# 09_RF_Loopback.net
KiCad netlist of a schematic drawn in Altium Designer
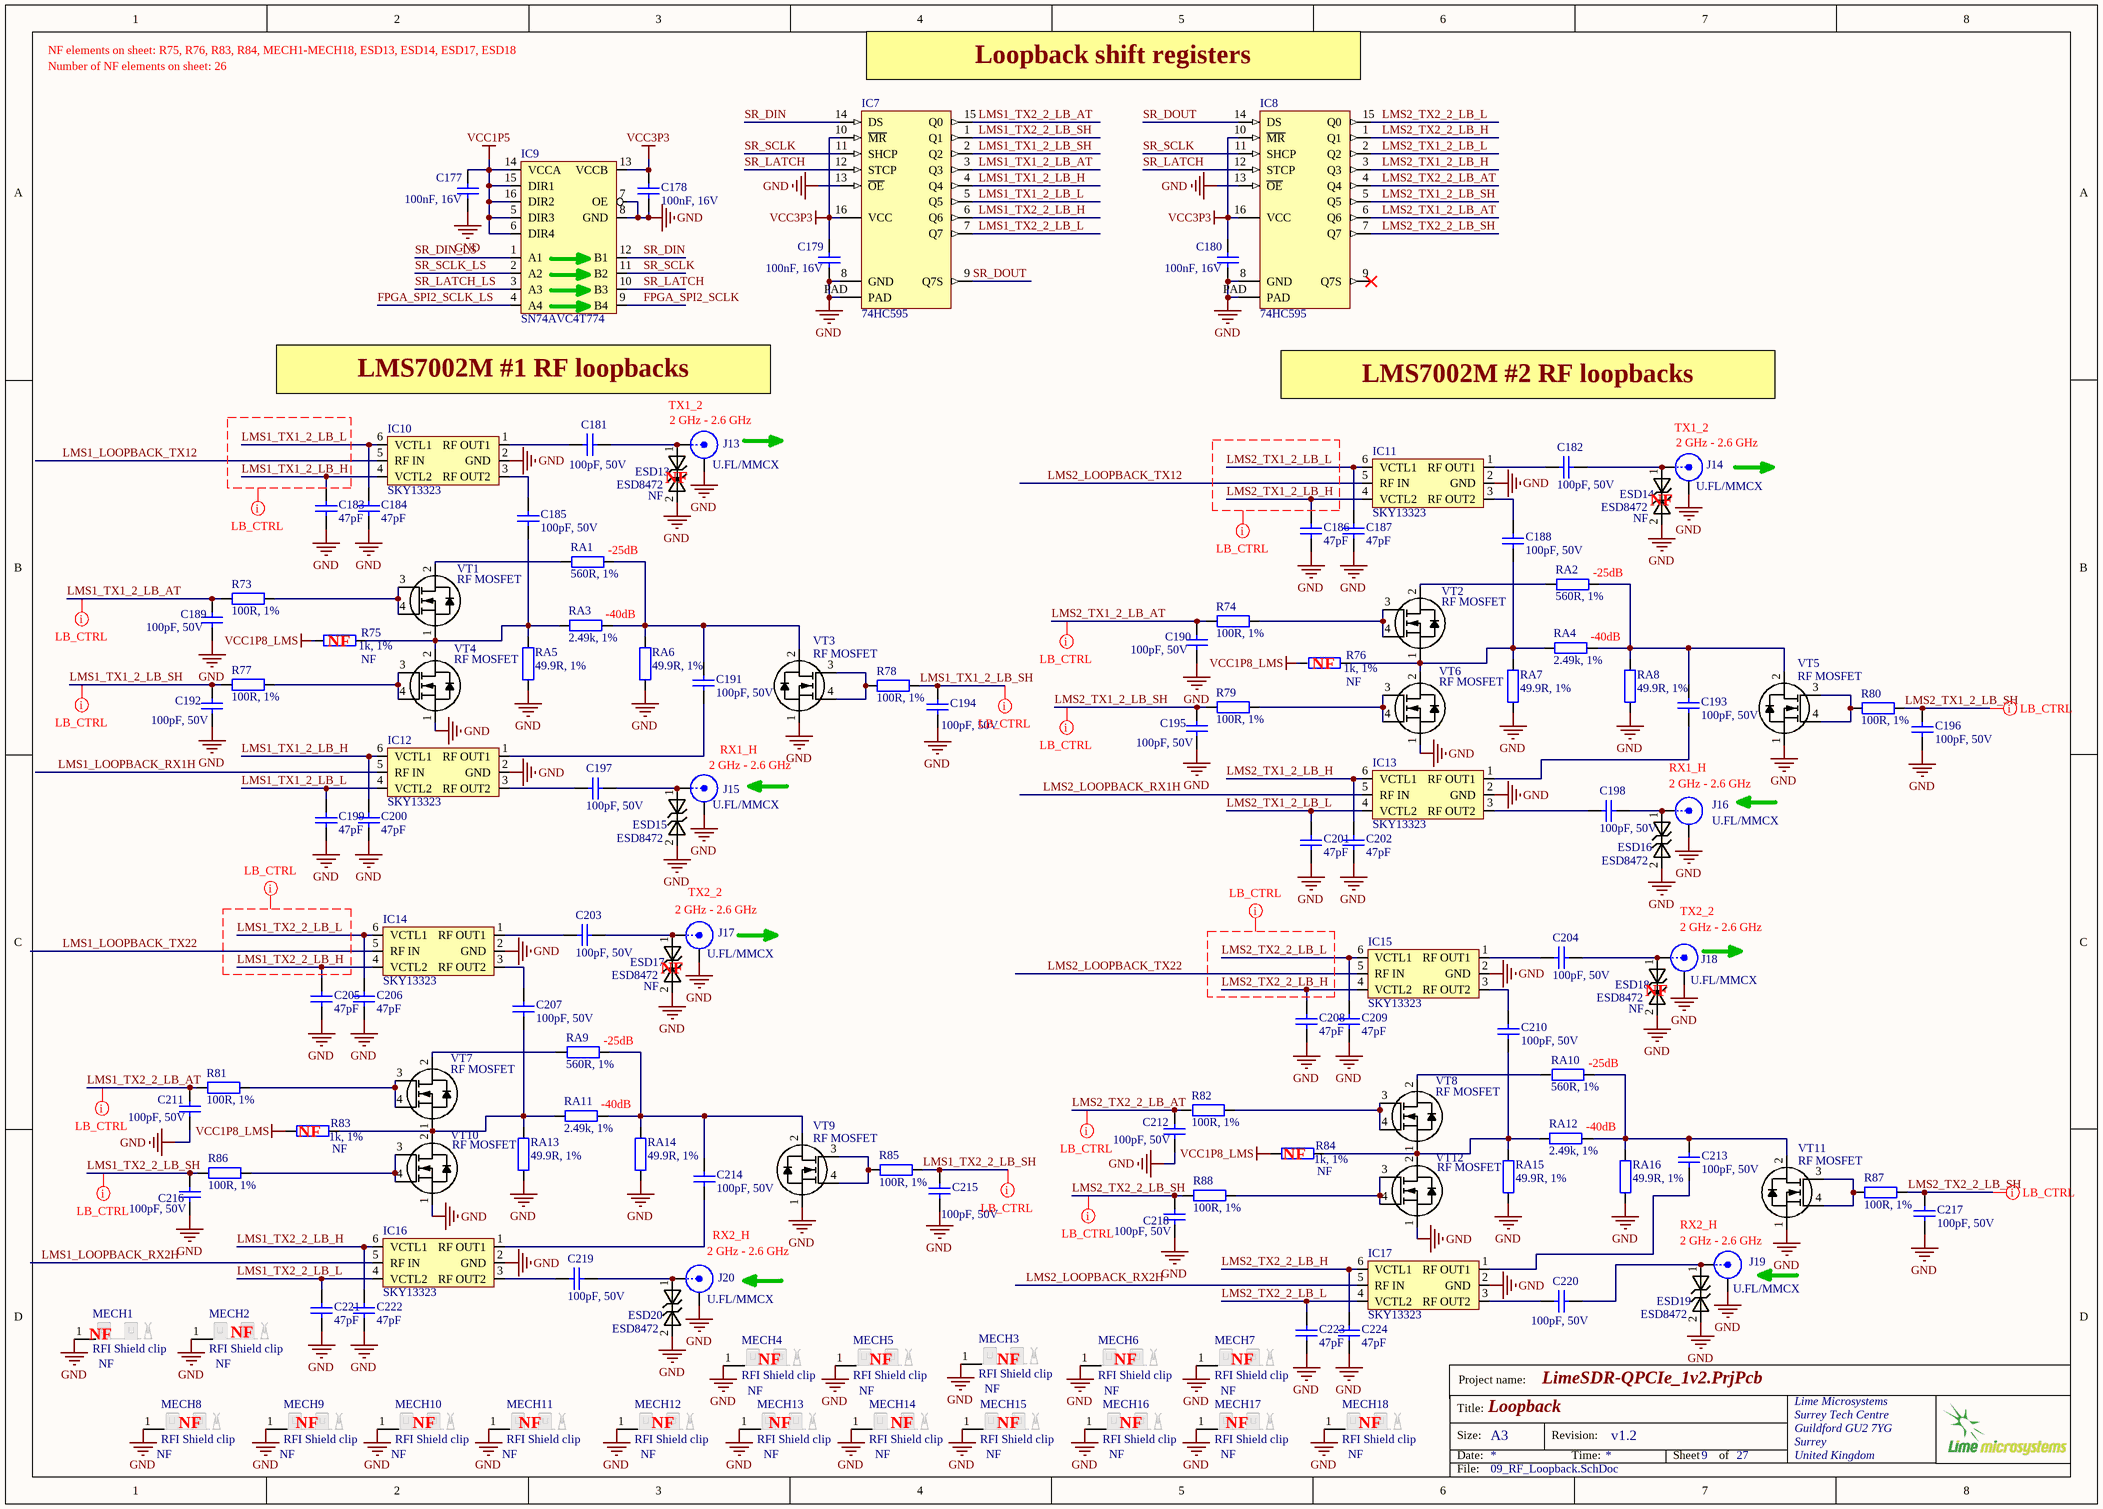
[diagram p0: 09_RF_Loopback.SchDoc]

(export (version "E")
  (design (tool "Eeschema 10.0.6"))
  (components
    (comp (ref "C177")
      (value "100nF, 16V")
      (footprint "CAP0402")
      (fields
        (field (name "MANUFACTURER") "Murata Electronics")
        (field (name "TOLERANCE") "10 %")
        (field (name "MANUFACTURER PART NUMBER") "GRM155R71C104KA88D")
      )
      (libsource (lib "LimeMicroAltiumLib_schLib") (part "Cap_0402"))
    )
    (comp (ref "C178")
      (value "100nF, 16V")
      (footprint "CAP0402")
      (fields
        (field (name "MANUFACTURER") "Murata Electronics")
        (field (name "TOLERANCE") "10 %")
        (field (name "MANUFACTURER PART NUMBER") "GRM155R71C104KA88D")
      )
      (libsource (lib "LimeMicroAltiumLib_schLib") (part "Cap_0402"))
    )
    (comp (ref "C179")
      (value "100nF, 16V")
      (footprint "CAP0402")
      (fields
        (field (name "MANUFACTURER") "Murata Electronics")
        (field (name "TOLERANCE") "10 %")
        (field (name "MANUFACTURER PART NUMBER") "GRM155R71C104KA88D")
      )
      (libsource (lib "LimeMicroAltiumLib_schLib") (part "Cap_0402"))
    )
    (comp (ref "C180")
      (value "100nF, 16V")
      (footprint "CAP0402")
      (fields
        (field (name "MANUFACTURER") "Murata Electronics")
        (field (name "TOLERANCE") "10 %")
        (field (name "MANUFACTURER PART NUMBER") "GRM155R71C104KA88D")
      )
      (libsource (lib "LimeMicroAltiumLib_schLib") (part "Cap_0402"))
    )
    (comp (ref "C181")
      (value "100pF, 50V")
      (footprint "CAP0402")
      (fields (field (name "TOLERANCE") "±5%") (field (name "MANUFACTURER") "Yageo"))
      (libsource (lib "LimeMicroAltiumLib_schLib") (part "Cap_0402"))
    )
    (comp (ref "C182")
      (value "100pF, 50V")
      (footprint "CAP0402")
      (fields (field (name "TOLERANCE") "±5%") (field (name "MANUFACTURER") "Yageo"))
      (libsource (lib "LimeMicroAltiumLib_schLib") (part "Cap_0402"))
    )
    (comp (ref "C183")
      (value "47pF")
      (footprint "CAP0402")
      (fields (field (name "TOLERANCE") "±1%") (field (name "MANUFACTURER") "TDK Corporation"))
      (libsource (lib "LimeMicroAltiumLib_schLib") (part "Cap_0402"))
    )
    (comp (ref "C184")
      (value "47pF")
      (footprint "CAP0402")
      (fields (field (name "TOLERANCE") "±1%") (field (name "MANUFACTURER") "TDK Corporation"))
      (libsource (lib "LimeMicroAltiumLib_schLib") (part "Cap_0402"))
    )
    (comp (ref "C185")
      (value "100pF, 50V")
      (footprint "CAP0402")
      (fields (field (name "TOLERANCE") "±5%") (field (name "MANUFACTURER") "Yageo"))
      (libsource (lib "LimeMicroAltiumLib_schLib") (part "Cap_0402"))
    )
    (comp (ref "C186")
      (value "47pF")
      (footprint "CAP0402")
      (fields (field (name "TOLERANCE") "±1%") (field (name "MANUFACTURER") "TDK Corporation"))
      (libsource (lib "LimeMicroAltiumLib_schLib") (part "Cap_0402"))
    )
    (comp (ref "C187")
      (value "47pF")
      (footprint "CAP0402")
      (fields (field (name "TOLERANCE") "±1%") (field (name "MANUFACTURER") "TDK Corporation"))
      (libsource (lib "LimeMicroAltiumLib_schLib") (part "Cap_0402"))
    )
    (comp (ref "C188")
      (value "100pF, 50V")
      (footprint "CAP0402")
      (fields (field (name "TOLERANCE") "±5%") (field (name "MANUFACTURER") "Yageo"))
      (libsource (lib "LimeMicroAltiumLib_schLib") (part "Cap_0402"))
    )
    (comp (ref "C189")
      (value "100pF, 50V")
      (footprint "CAP0402")
      (fields (field (name "TOLERANCE") "±5%") (field (name "MANUFACTURER") "Yageo"))
      (libsource (lib "LimeMicroAltiumLib_schLib") (part "Cap_0402"))
    )
    (comp (ref "C190")
      (value "100pF, 50V")
      (footprint "CAP0402")
      (fields (field (name "TOLERANCE") "±5%") (field (name "MANUFACTURER") "Yageo"))
      (libsource (lib "LimeMicroAltiumLib_schLib") (part "Cap_0402"))
    )
    (comp (ref "C191")
      (value "100pF, 50V")
      (footprint "CAP0402")
      (fields (field (name "TOLERANCE") "±5%") (field (name "MANUFACTURER") "Yageo"))
      (libsource (lib "LimeMicroAltiumLib_schLib") (part "Cap_0402"))
    )
    (comp (ref "C192")
      (value "100pF, 50V")
      (footprint "CAP0402")
      (fields (field (name "TOLERANCE") "±5%") (field (name "MANUFACTURER") "Yageo"))
      (libsource (lib "LimeMicroAltiumLib_schLib") (part "Cap_0402"))
    )
    (comp (ref "C193")
      (value "100pF, 50V")
      (footprint "CAP0402")
      (fields (field (name "TOLERANCE") "±5%") (field (name "MANUFACTURER") "Yageo"))
      (libsource (lib "LimeMicroAltiumLib_schLib") (part "Cap_0402"))
    )
    (comp (ref "C194")
      (value "100pF, 50V")
      (footprint "CAP0402")
      (fields (field (name "TOLERANCE") "±5%") (field (name "MANUFACTURER") "Yageo"))
      (libsource (lib "LimeMicroAltiumLib_schLib") (part "Cap_0402"))
    )
    (comp (ref "C195")
      (value "100pF, 50V")
      (footprint "CAP0402")
      (fields (field (name "TOLERANCE") "±5%") (field (name "MANUFACTURER") "Yageo"))
      (libsource (lib "LimeMicroAltiumLib_schLib") (part "Cap_0402"))
    )
    (comp (ref "C196")
      (value "100pF, 50V")
      (footprint "CAP0402")
      (fields (field (name "TOLERANCE") "±5%") (field (name "MANUFACTURER") "Yageo"))
      (libsource (lib "LimeMicroAltiumLib_schLib") (part "Cap_0402"))
    )
    (comp (ref "C197")
      (value "100pF, 50V")
      (footprint "CAP0402")
      (fields (field (name "TOLERANCE") "±5%") (field (name "MANUFACTURER") "Yageo"))
      (libsource (lib "LimeMicroAltiumLib_schLib") (part "Cap_0402"))
    )
    (comp (ref "C198")
      (value "100pF, 50V")
      (footprint "CAP0402")
      (fields (field (name "TOLERANCE") "±5%") (field (name "MANUFACTURER") "Yageo"))
      (libsource (lib "LimeMicroAltiumLib_schLib") (part "Cap_0402"))
    )
    (comp (ref "C199")
      (value "47pF")
      (footprint "CAP0402")
      (fields (field (name "TOLERANCE") "±1%") (field (name "MANUFACTURER") "TDK Corporation"))
      (libsource (lib "LimeMicroAltiumLib_schLib") (part "Cap_0402"))
    )
    (comp (ref "C200")
      (value "47pF")
      (footprint "CAP0402")
      (fields (field (name "TOLERANCE") "±1%") (field (name "MANUFACTURER") "TDK Corporation"))
      (libsource (lib "LimeMicroAltiumLib_schLib") (part "Cap_0402"))
    )
    (comp (ref "C201")
      (value "47pF")
      (footprint "CAP0402")
      (fields (field (name "TOLERANCE") "±1%") (field (name "MANUFACTURER") "TDK Corporation"))
      (libsource (lib "LimeMicroAltiumLib_schLib") (part "Cap_0402"))
    )
    (comp (ref "C202")
      (value "47pF")
      (footprint "CAP0402")
      (fields (field (name "TOLERANCE") "±1%") (field (name "MANUFACTURER") "TDK Corporation"))
      (libsource (lib "LimeMicroAltiumLib_schLib") (part "Cap_0402"))
    )
    (comp (ref "C203")
      (value "100pF, 50V")
      (footprint "CAP0402")
      (fields (field (name "TOLERANCE") "±5%") (field (name "MANUFACTURER") "Yageo"))
      (libsource (lib "LimeMicroAltiumLib_schLib") (part "Cap_0402"))
    )
    (comp (ref "C204")
      (value "100pF, 50V")
      (footprint "CAP0402")
      (fields (field (name "TOLERANCE") "±5%") (field (name "MANUFACTURER") "Yageo"))
      (libsource (lib "LimeMicroAltiumLib_schLib") (part "Cap_0402"))
    )
    (comp (ref "C205")
      (value "47pF")
      (footprint "CAP0402")
      (fields (field (name "TOLERANCE") "±1%") (field (name "MANUFACTURER") "TDK Corporation"))
      (libsource (lib "LimeMicroAltiumLib_schLib") (part "Cap_0402"))
    )
    (comp (ref "C206")
      (value "47pF")
      (footprint "CAP0402")
      (fields (field (name "TOLERANCE") "±1%") (field (name "MANUFACTURER") "TDK Corporation"))
      (libsource (lib "LimeMicroAltiumLib_schLib") (part "Cap_0402"))
    )
    (comp (ref "C207")
      (value "100pF, 50V")
      (footprint "CAP0402")
      (fields (field (name "TOLERANCE") "±5%") (field (name "MANUFACTURER") "Yageo"))
      (libsource (lib "LimeMicroAltiumLib_schLib") (part "Cap_0402"))
    )
    (comp (ref "C208")
      (value "47pF")
      (footprint "CAP0402")
      (fields (field (name "TOLERANCE") "±1%") (field (name "MANUFACTURER") "TDK Corporation"))
      (libsource (lib "LimeMicroAltiumLib_schLib") (part "Cap_0402"))
    )
    (comp (ref "C209")
      (value "47pF")
      (footprint "CAP0402")
      (fields (field (name "TOLERANCE") "±1%") (field (name "MANUFACTURER") "TDK Corporation"))
      (libsource (lib "LimeMicroAltiumLib_schLib") (part "Cap_0402"))
    )
    (comp (ref "C210")
      (value "100pF, 50V")
      (footprint "CAP0402")
      (fields (field (name "TOLERANCE") "±5%") (field (name "MANUFACTURER") "Yageo"))
      (libsource (lib "LimeMicroAltiumLib_schLib") (part "Cap_0402"))
    )
    (comp (ref "C211")
      (value "100pF, 50V")
      (footprint "CAP0402")
      (fields (field (name "TOLERANCE") "±5%") (field (name "MANUFACTURER") "Yageo"))
      (libsource (lib "LimeMicroAltiumLib_schLib") (part "Cap_0402"))
    )
    (comp (ref "C212")
      (value "100pF, 50V")
      (footprint "CAP0402")
      (fields (field (name "TOLERANCE") "±5%") (field (name "MANUFACTURER") "Yageo"))
      (libsource (lib "LimeMicroAltiumLib_schLib") (part "Cap_0402"))
    )
    (comp (ref "C213")
      (value "100pF, 50V")
      (footprint "CAP0402")
      (fields (field (name "TOLERANCE") "±5%") (field (name "MANUFACTURER") "Yageo"))
      (libsource (lib "LimeMicroAltiumLib_schLib") (part "Cap_0402"))
    )
    (comp (ref "C214")
      (value "100pF, 50V")
      (footprint "CAP0402")
      (fields (field (name "TOLERANCE") "±5%") (field (name "MANUFACTURER") "Yageo"))
      (libsource (lib "LimeMicroAltiumLib_schLib") (part "Cap_0402"))
    )
    (comp (ref "C215")
      (value "100pF, 50V")
      (footprint "CAP0402")
      (fields (field (name "TOLERANCE") "±5%") (field (name "MANUFACTURER") "Yageo"))
      (libsource (lib "LimeMicroAltiumLib_schLib") (part "Cap_0402"))
    )
    (comp (ref "C216")
      (value "100pF, 50V")
      (footprint "CAP0402")
      (fields (field (name "TOLERANCE") "±5%") (field (name "MANUFACTURER") "Yageo"))
      (libsource (lib "LimeMicroAltiumLib_schLib") (part "Cap_0402"))
    )
    (comp (ref "C217")
      (value "100pF, 50V")
      (footprint "CAP0402")
      (fields (field (name "TOLERANCE") "±5%") (field (name "MANUFACTURER") "Yageo"))
      (libsource (lib "LimeMicroAltiumLib_schLib") (part "Cap_0402"))
    )
    (comp (ref "C218")
      (value "100pF, 50V")
      (footprint "CAP0402")
      (fields (field (name "TOLERANCE") "±5%") (field (name "MANUFACTURER") "Yageo"))
      (libsource (lib "LimeMicroAltiumLib_schLib") (part "Cap_0402"))
    )
    (comp (ref "C219")
      (value "100pF, 50V")
      (footprint "CAP0402")
      (fields (field (name "TOLERANCE") "±5%") (field (name "MANUFACTURER") "Yageo"))
      (libsource (lib "LimeMicroAltiumLib_schLib") (part "Cap_0402"))
    )
    (comp (ref "C220")
      (value "100pF, 50V")
      (footprint "CAP0402")
      (fields (field (name "TOLERANCE") "±5%") (field (name "MANUFACTURER") "Yageo"))
      (libsource (lib "LimeMicroAltiumLib_schLib") (part "Cap_0402"))
    )
    (comp (ref "C221")
      (value "47pF")
      (footprint "CAP0402")
      (fields (field (name "TOLERANCE") "±1%") (field (name "MANUFACTURER") "TDK Corporation"))
      (libsource (lib "LimeMicroAltiumLib_schLib") (part "Cap_0402"))
    )
    (comp (ref "C222")
      (value "47pF")
      (footprint "CAP0402")
      (fields (field (name "TOLERANCE") "±1%") (field (name "MANUFACTURER") "TDK Corporation"))
      (libsource (lib "LimeMicroAltiumLib_schLib") (part "Cap_0402"))
    )
    (comp (ref "C223")
      (value "47pF")
      (footprint "CAP0402")
      (fields (field (name "TOLERANCE") "±1%") (field (name "MANUFACTURER") "TDK Corporation"))
      (libsource (lib "LimeMicroAltiumLib_schLib") (part "Cap_0402"))
    )
    (comp (ref "C224")
      (value "47pF")
      (footprint "CAP0402")
      (fields (field (name "TOLERANCE") "±1%") (field (name "MANUFACTURER") "TDK Corporation"))
      (libsource (lib "LimeMicroAltiumLib_schLib") (part "Cap_0402"))
    )
    (comp (ref "ESD13")
      (value "ESD8472")
      (footprint "ESD8472_X3DFN2")
      (fields
        (field (name "MANUFACTURER") "ON Semiconductor")
        (field (name "MANUFACTURER PART NUMBER") "ESD8472MUT5G")
        (field (name "ASSEMBLY INFO") "NF")
      )
      (libsource (lib "LimeMicroAltiumLib_schLib") (part "ESD8472"))
    )
    (comp (ref "ESD14")
      (value "ESD8472")
      (footprint "ESD8472_X3DFN2")
      (fields
        (field (name "MANUFACTURER") "ON Semiconductor")
        (field (name "MANUFACTURER PART NUMBER") "ESD8472MUT5G")
        (field (name "ASSEMBLY INFO") "NF")
      )
      (libsource (lib "LimeMicroAltiumLib_schLib") (part "ESD8472"))
    )
    (comp (ref "ESD15")
      (value "ESD8472")
      (footprint "ESD8472_X3DFN2")
      (fields
        (field (name "MANUFACTURER") "ON Semiconductor")
        (field (name "MANUFACTURER PART NUMBER") "ESD8472MUT5G")
      )
      (libsource (lib "LimeMicroAltiumLib_schLib") (part "ESD8472"))
    )
    (comp (ref "ESD16")
      (value "ESD8472")
      (footprint "ESD8472_X3DFN2")
      (fields
        (field (name "MANUFACTURER") "ON Semiconductor")
        (field (name "MANUFACTURER PART NUMBER") "ESD8472MUT5G")
      )
      (libsource (lib "LimeMicroAltiumLib_schLib") (part "ESD8472"))
    )
    (comp (ref "ESD17")
      (value "ESD8472")
      (footprint "ESD8472_X3DFN2")
      (fields
        (field (name "MANUFACTURER") "ON Semiconductor")
        (field (name "MANUFACTURER PART NUMBER") "ESD8472MUT5G")
        (field (name "ASSEMBLY INFO") "NF")
      )
      (libsource (lib "LimeMicroAltiumLib_schLib") (part "ESD8472"))
    )
    (comp (ref "ESD18")
      (value "ESD8472")
      (footprint "ESD8472_X3DFN2")
      (fields
        (field (name "MANUFACTURER") "ON Semiconductor")
        (field (name "MANUFACTURER PART NUMBER") "ESD8472MUT5G")
        (field (name "ASSEMBLY INFO") "NF")
      )
      (libsource (lib "LimeMicroAltiumLib_schLib") (part "ESD8472"))
    )
    (comp (ref "ESD19")
      (value "ESD8472")
      (footprint "ESD8472_X3DFN2")
      (fields
        (field (name "MANUFACTURER") "ON Semiconductor")
        (field (name "MANUFACTURER PART NUMBER") "ESD8472MUT5G")
      )
      (libsource (lib "LimeMicroAltiumLib_schLib") (part "ESD8472"))
    )
    (comp (ref "ESD20")
      (value "ESD8472")
      (footprint "ESD8472_X3DFN2")
      (fields
        (field (name "MANUFACTURER") "ON Semiconductor")
        (field (name "MANUFACTURER PART NUMBER") "ESD8472MUT5G")
      )
      (libsource (lib "LimeMicroAltiumLib_schLib") (part "ESD8472"))
    )
    (comp (ref "IC7")
      (value "74HC595")
      (footprint "74HC595BQ,115")
      (fields (field (name "MANUFACTURER") "Nexperia USA Inc."))
      (libsource (lib "LimeMicroAltiumLib_schLib") (part "74HC595BQ,115"))
    )
    (comp (ref "IC8")
      (value "74HC595")
      (footprint "74HC595BQ,115")
      (fields (field (name "MANUFACTURER") "Nexperia USA Inc."))
      (libsource (lib "LimeMicroAltiumLib_schLib") (part "74HC595BQ,115"))
    )
    (comp (ref "IC9")
      (value "SN74AVC4T774")
      (footprint "SN74AVC4T774")
      (fields (field (name "MANUFACTURER") "Texas Instruments"))
      (libsource (lib "LimeMicroAltiumLib_schLib") (part "SN74AVC4T774"))
    )
    (comp (ref "IC10")
      (value "SKY13323")
      (footprint "SKY13323-378LF")
      (description "SKY13323-378LF: 0.1-3.0 GHz GaAs SPDT Switch")
      (fields (field (name "MANUFACTURER") "Skyworks Solutions Inc."))
      (libsource (lib "LimeMicroAltiumLib_schLib") (part "SKY13323"))
    )
    (comp (ref "IC11")
      (value "SKY13323")
      (footprint "SKY13323-378LF")
      (description "SKY13323-378LF: 0.1-3.0 GHz GaAs SPDT Switch")
      (fields (field (name "MANUFACTURER") "Skyworks Solutions Inc."))
      (libsource (lib "LimeMicroAltiumLib_schLib") (part "SKY13323"))
    )
    (comp (ref "IC12")
      (value "SKY13323")
      (footprint "SKY13323-378LF")
      (description "SKY13323-378LF: 0.1-3.0 GHz GaAs SPDT Switch")
      (fields (field (name "MANUFACTURER") "Skyworks Solutions Inc."))
      (libsource (lib "LimeMicroAltiumLib_schLib") (part "SKY13323"))
    )
    (comp (ref "IC13")
      (value "SKY13323")
      (footprint "SKY13323-378LF")
      (description "SKY13323-378LF: 0.1-3.0 GHz GaAs SPDT Switch")
      (fields (field (name "MANUFACTURER") "Skyworks Solutions Inc."))
      (libsource (lib "LimeMicroAltiumLib_schLib") (part "SKY13323"))
    )
    (comp (ref "IC14")
      (value "SKY13323")
      (footprint "SKY13323-378LF")
      (description "SKY13323-378LF: 0.1-3.0 GHz GaAs SPDT Switch")
      (fields (field (name "MANUFACTURER") "Skyworks Solutions Inc."))
      (libsource (lib "LimeMicroAltiumLib_schLib") (part "SKY13323"))
    )
    (comp (ref "IC15")
      (value "SKY13323")
      (footprint "SKY13323-378LF")
      (description "SKY13323-378LF: 0.1-3.0 GHz GaAs SPDT Switch")
      (fields (field (name "MANUFACTURER") "Skyworks Solutions Inc."))
      (libsource (lib "LimeMicroAltiumLib_schLib") (part "SKY13323"))
    )
    (comp (ref "IC16")
      (value "SKY13323")
      (footprint "SKY13323-378LF")
      (description "SKY13323-378LF: 0.1-3.0 GHz GaAs SPDT Switch")
      (fields (field (name "MANUFACTURER") "Skyworks Solutions Inc."))
      (libsource (lib "LimeMicroAltiumLib_schLib") (part "SKY13323"))
    )
    (comp (ref "IC17")
      (value "SKY13323")
      (footprint "SKY13323-378LF")
      (description "SKY13323-378LF: 0.1-3.0 GHz GaAs SPDT Switch")
      (fields (field (name "MANUFACTURER") "Skyworks Solutions Inc."))
      (libsource (lib "LimeMicroAltiumLib_schLib") (part "SKY13323"))
    )
    (comp (ref "J13")
      (value "U.FL/MMCX")
      (footprint "MMCX_UFL_conn_u")
      (description "CONN UMC RCPT STR 50 OHM SMD")
      (fields (field (name "MANUFACTURER") "Molex, LLC"))
      (libsource (lib "LimeMicroAltiumLib_schLib") (part "RF_IF_connector"))
    )
    (comp (ref "J14")
      (value "U.FL/MMCX")
      (footprint "MMCX_UFL_conn_u")
      (description "CONN UMC RCPT STR 50 OHM SMD")
      (fields (field (name "MANUFACTURER") "Molex, LLC"))
      (libsource (lib "LimeMicroAltiumLib_schLib") (part "RF_IF_connector"))
    )
    (comp (ref "J15")
      (value "U.FL/MMCX")
      (footprint "MMCX_UFL_conn_u")
      (description "CONN UMC RCPT STR 50 OHM SMD")
      (fields (field (name "MANUFACTURER") "Molex, LLC"))
      (libsource (lib "LimeMicroAltiumLib_schLib") (part "RF_IF_connector"))
    )
    (comp (ref "J16")
      (value "U.FL/MMCX")
      (footprint "MMCX_UFL_conn_u")
      (description "CONN UMC RCPT STR 50 OHM SMD")
      (fields (field (name "MANUFACTURER") "Molex, LLC"))
      (libsource (lib "LimeMicroAltiumLib_schLib") (part "RF_IF_connector"))
    )
    (comp (ref "J17")
      (value "U.FL/MMCX")
      (footprint "MMCX_UFL_conn_u")
      (description "CONN UMC RCPT STR 50 OHM SMD")
      (fields (field (name "MANUFACTURER") "Molex, LLC"))
      (libsource (lib "LimeMicroAltiumLib_schLib") (part "RF_IF_connector"))
    )
    (comp (ref "J18")
      (value "U.FL/MMCX")
      (footprint "MMCX_UFL_conn_u")
      (description "CONN UMC RCPT STR 50 OHM SMD")
      (fields (field (name "MANUFACTURER") "Molex, LLC"))
      (libsource (lib "LimeMicroAltiumLib_schLib") (part "RF_IF_connector"))
    )
    (comp (ref "J19")
      (value "U.FL/MMCX")
      (footprint "MMCX_UFL_conn_u")
      (description "CONN UMC RCPT STR 50 OHM SMD")
      (fields (field (name "MANUFACTURER") "Molex, LLC"))
      (libsource (lib "LimeMicroAltiumLib_schLib") (part "RF_IF_connector"))
    )
    (comp (ref "J20")
      (value "U.FL/MMCX")
      (footprint "MMCX_UFL_conn_u")
      (description "CONN UMC RCPT STR 50 OHM SMD")
      (fields (field (name "MANUFACTURER") "Molex, LLC"))
      (libsource (lib "LimeMicroAltiumLib_schLib") (part "RF_IF_connector"))
    )
    (comp (ref "MECH1")
      (value "RFI Shield clip")
      (footprint "RFI_SHIELD_CLPS_MINI")
      (fields (field (name "MANUFACTURER") "HARWIN") (field (name "ASSEMBLY INFO") "NF"))
      (libsource (lib "LimeMicroAltiumLib_schLib") (part "RFI_SHIELD_CLIP"))
    )
    (comp (ref "MECH2")
      (value "RFI Shield clip")
      (footprint "RFI_SHIELD_CLPS_MINI")
      (fields (field (name "MANUFACTURER") "HARWIN") (field (name "ASSEMBLY INFO") "NF"))
      (libsource (lib "LimeMicroAltiumLib_schLib") (part "RFI_SHIELD_CLIP"))
    )
    (comp (ref "MECH3")
      (value "RFI Shield clip")
      (footprint "RFI_SHIELD_CLPS_MINI")
      (fields (field (name "MANUFACTURER") "HARWIN") (field (name "ASSEMBLY INFO") "NF"))
      (libsource (lib "LimeMicroAltiumLib_schLib") (part "RFI_SHIELD_CLIP"))
    )
    (comp (ref "MECH4")
      (value "RFI Shield clip")
      (footprint "RFI_SHIELD_CLPS_MINI")
      (fields (field (name "MANUFACTURER") "HARWIN") (field (name "ASSEMBLY INFO") "NF"))
      (libsource (lib "LimeMicroAltiumLib_schLib") (part "RFI_SHIELD_CLIP"))
    )
    (comp (ref "MECH5")
      (value "RFI Shield clip")
      (footprint "RFI_SHIELD_CLPS_MINI")
      (fields (field (name "MANUFACTURER") "HARWIN") (field (name "ASSEMBLY INFO") "NF"))
      (libsource (lib "LimeMicroAltiumLib_schLib") (part "RFI_SHIELD_CLIP"))
    )
    (comp (ref "MECH6")
      (value "RFI Shield clip")
      (footprint "RFI_SHIELD_CLPS_MINI")
      (fields (field (name "MANUFACTURER") "HARWIN") (field (name "ASSEMBLY INFO") "NF"))
      (libsource (lib "LimeMicroAltiumLib_schLib") (part "RFI_SHIELD_CLIP"))
    )
    (comp (ref "MECH7")
      (value "RFI Shield clip")
      (footprint "RFI_SHIELD_CLPS_MINI")
      (fields (field (name "MANUFACTURER") "HARWIN") (field (name "ASSEMBLY INFO") "NF"))
      (libsource (lib "LimeMicroAltiumLib_schLib") (part "RFI_SHIELD_CLIP"))
    )
    (comp (ref "MECH8")
      (value "RFI Shield clip")
      (footprint "RFI_SHIELD_CLPS_MINI")
      (fields (field (name "MANUFACTURER") "HARWIN") (field (name "ASSEMBLY INFO") "NF"))
      (libsource (lib "LimeMicroAltiumLib_schLib") (part "RFI_SHIELD_CLIP"))
    )
    (comp (ref "MECH9")
      (value "RFI Shield clip")
      (footprint "RFI_SHIELD_CLPS_MINI")
      (fields (field (name "MANUFACTURER") "HARWIN") (field (name "ASSEMBLY INFO") "NF"))
      (libsource (lib "LimeMicroAltiumLib_schLib") (part "RFI_SHIELD_CLIP"))
    )
    (comp (ref "MECH10")
      (value "RFI Shield clip")
      (footprint "RFI_SHIELD_CLPS_MINI")
      (fields (field (name "MANUFACTURER") "HARWIN") (field (name "ASSEMBLY INFO") "NF"))
      (libsource (lib "LimeMicroAltiumLib_schLib") (part "RFI_SHIELD_CLIP"))
    )
    (comp (ref "MECH11")
      (value "RFI Shield clip")
      (footprint "RFI_SHIELD_CLPS_MINI")
      (fields (field (name "MANUFACTURER") "HARWIN") (field (name "ASSEMBLY INFO") "NF"))
      (libsource (lib "LimeMicroAltiumLib_schLib") (part "RFI_SHIELD_CLIP"))
    )
    (comp (ref "MECH12")
      (value "RFI Shield clip")
      (footprint "RFI_SHIELD_CLPS_MINI")
      (fields (field (name "MANUFACTURER") "HARWIN") (field (name "ASSEMBLY INFO") "NF"))
      (libsource (lib "LimeMicroAltiumLib_schLib") (part "RFI_SHIELD_CLIP"))
    )
    (comp (ref "MECH13")
      (value "RFI Shield clip")
      (footprint "RFI_SHIELD_CLPS_MINI")
      (fields (field (name "MANUFACTURER") "HARWIN") (field (name "ASSEMBLY INFO") "NF"))
      (libsource (lib "LimeMicroAltiumLib_schLib") (part "RFI_SHIELD_CLIP"))
    )
    (comp (ref "MECH14")
      (value "RFI Shield clip")
      (footprint "RFI_SHIELD_CLPS_MINI")
      (fields (field (name "MANUFACTURER") "HARWIN") (field (name "ASSEMBLY INFO") "NF"))
      (libsource (lib "LimeMicroAltiumLib_schLib") (part "RFI_SHIELD_CLIP"))
    )
    (comp (ref "MECH15")
      (value "RFI Shield clip")
      (footprint "RFI_SHIELD_CLPS_MINI")
      (fields (field (name "MANUFACTURER") "HARWIN") (field (name "ASSEMBLY INFO") "NF"))
      (libsource (lib "LimeMicroAltiumLib_schLib") (part "RFI_SHIELD_CLIP"))
    )
    (comp (ref "MECH16")
      (value "RFI Shield clip")
      (footprint "RFI_SHIELD_CLPS_MINI")
      (fields (field (name "MANUFACTURER") "HARWIN") (field (name "ASSEMBLY INFO") "NF"))
      (libsource (lib "LimeMicroAltiumLib_schLib") (part "RFI_SHIELD_CLIP"))
    )
    (comp (ref "MECH17")
      (value "RFI Shield clip")
      (footprint "RFI_SHIELD_CLPS_MINI")
      (fields (field (name "MANUFACTURER") "HARWIN") (field (name "ASSEMBLY INFO") "NF"))
      (libsource (lib "LimeMicroAltiumLib_schLib") (part "RFI_SHIELD_CLIP"))
    )
    (comp (ref "MECH18")
      (value "RFI Shield clip")
      (footprint "RFI_SHIELD_CLPS_MINI")
      (fields (field (name "MANUFACTURER") "HARWIN") (field (name "ASSEMBLY INFO") "NF"))
      (libsource (lib "LimeMicroAltiumLib_schLib") (part "RFI_SHIELD_CLIP"))
    )
    (comp (ref "R73")
      (value "100R, 1%")
      (footprint "RES0402")
      (fields (field (name "TOLERANCE") "±1%") (field (name "MANUFACTURER") "Stackpole Electronics Inc."))
      (libsource (lib "LimeFPGAboard_schLib") (part "Res_0402"))
    )
    (comp (ref "R74")
      (value "100R, 1%")
      (footprint "RES0402")
      (fields (field (name "TOLERANCE") "±1%") (field (name "MANUFACTURER") "Stackpole Electronics Inc."))
      (libsource (lib "LimeFPGAboard_schLib") (part "Res_0402"))
    )
    (comp (ref "R75")
      (value "1k, 1%")
      (footprint "RES0402")
      (fields
        (field (name "ASSEMBLY INFO") "NF")
        (field (name "MANUFACTURER") "Stackpole Electronics Inc")
        (field (name "TOLERANCE") "±1%")
      )
      (libsource (lib "LimeMicroAltiumLib_schLib") (part "Res_0402"))
    )
    (comp (ref "R76")
      (value "1k, 1%")
      (footprint "RES0402")
      (fields
        (field (name "ASSEMBLY INFO") "NF")
        (field (name "MANUFACTURER") "Stackpole Electronics Inc")
        (field (name "TOLERANCE") "±1%")
      )
      (libsource (lib "LimeMicroAltiumLib_schLib") (part "Res_0402"))
    )
    (comp (ref "R77")
      (value "100R, 1%")
      (footprint "RES0402")
      (fields (field (name "TOLERANCE") "±1%") (field (name "MANUFACTURER") "Stackpole Electronics Inc."))
      (libsource (lib "LimeFPGAboard_schLib") (part "Res_0402"))
    )
    (comp (ref "R78")
      (value "100R, 1%")
      (footprint "RES0402")
      (fields (field (name "TOLERANCE") "±1%") (field (name "MANUFACTURER") "Stackpole Electronics Inc."))
      (libsource (lib "LimeFPGAboard_schLib") (part "Res_0402"))
    )
    (comp (ref "R79")
      (value "100R, 1%")
      (footprint "RES0402")
      (fields (field (name "TOLERANCE") "±1%") (field (name "MANUFACTURER") "Stackpole Electronics Inc."))
      (libsource (lib "LimeFPGAboard_schLib") (part "Res_0402"))
    )
    (comp (ref "R80")
      (value "100R, 1%")
      (footprint "RES0402")
      (fields (field (name "TOLERANCE") "±1%") (field (name "MANUFACTURER") "Stackpole Electronics Inc."))
      (libsource (lib "LimeFPGAboard_schLib") (part "Res_0402"))
    )
    (comp (ref "R81")
      (value "100R, 1%")
      (footprint "RES0402")
      (fields (field (name "TOLERANCE") "±1%") (field (name "MANUFACTURER") "Stackpole Electronics Inc."))
      (libsource (lib "LimeFPGAboard_schLib") (part "Res_0402"))
    )
    (comp (ref "R82")
      (value "100R, 1%")
      (footprint "RES0402")
      (fields (field (name "TOLERANCE") "±1%") (field (name "MANUFACTURER") "Stackpole Electronics Inc."))
      (libsource (lib "LimeFPGAboard_schLib") (part "Res_0402"))
    )
    (comp (ref "R83")
      (value "1k, 1%")
      (footprint "RES0402")
      (fields
        (field (name "ASSEMBLY INFO") "NF")
        (field (name "MANUFACTURER") "Stackpole Electronics Inc")
        (field (name "TOLERANCE") "±1%")
      )
      (libsource (lib "LimeMicroAltiumLib_schLib") (part "Res_0402"))
    )
    (comp (ref "R84")
      (value "1k, 1%")
      (footprint "RES0402")
      (fields
        (field (name "ASSEMBLY INFO") "NF")
        (field (name "MANUFACTURER") "Stackpole Electronics Inc")
        (field (name "TOLERANCE") "±1%")
      )
      (libsource (lib "LimeMicroAltiumLib_schLib") (part "Res_0402"))
    )
    (comp (ref "R85")
      (value "100R, 1%")
      (footprint "RES0402")
      (fields (field (name "TOLERANCE") "±1%") (field (name "MANUFACTURER") "Stackpole Electronics Inc."))
      (libsource (lib "LimeFPGAboard_schLib") (part "Res_0402"))
    )
    (comp (ref "R86")
      (value "100R, 1%")
      (footprint "RES0402")
      (fields (field (name "TOLERANCE") "±1%") (field (name "MANUFACTURER") "Stackpole Electronics Inc."))
      (libsource (lib "LimeFPGAboard_schLib") (part "Res_0402"))
    )
    (comp (ref "R87")
      (value "100R, 1%")
      (footprint "RES0402")
      (fields (field (name "TOLERANCE") "±1%") (field (name "MANUFACTURER") "Stackpole Electronics Inc."))
      (libsource (lib "LimeFPGAboard_schLib") (part "Res_0402"))
    )
    (comp (ref "R88")
      (value "100R, 1%")
      (footprint "RES0402")
      (fields (field (name "TOLERANCE") "±1%") (field (name "MANUFACTURER") "Stackpole Electronics Inc."))
      (libsource (lib "LimeFPGAboard_schLib") (part "Res_0402"))
    )
    (comp (ref "RA1")
      (value "560R, 1%")
      (footprint "RES0402")
      (fields
        (field (name "MANUFACTURER PART NUMBER") "CRCW0402560RFKED")
        (field (name "TOLERANCE") "±1%")
        (field (name "MANUFACTURER") "Vishay Dale")
      )
      (libsource (lib "LimeMicroAltiumLib_schLib") (part "Res_0402"))
    )
    (comp (ref "RA2")
      (value "560R, 1%")
      (footprint "RES0402")
      (fields
        (field (name "MANUFACTURER PART NUMBER") "CRCW0402560RFKED")
        (field (name "TOLERANCE") "±1%")
        (field (name "MANUFACTURER") "Vishay Dale")
      )
      (libsource (lib "LimeMicroAltiumLib_schLib") (part "Res_0402"))
    )
    (comp (ref "RA3")
      (value "2.49k, 1%")
      (footprint "RES0402")
      (fields
        (field (name "TOLERANCE") "±1%")
        (field (name "MANUFACTURER PART NUMBER") "RC0402FR-072K49L")
        (field (name "MANUFACTURER") "Yageo")
      )
      (libsource (lib "LimeMicroAltiumLib_schLib") (part "Res_0402"))
    )
    (comp (ref "RA4")
      (value "2.49k, 1%")
      (footprint "RES0402")
      (fields
        (field (name "TOLERANCE") "±1%")
        (field (name "MANUFACTURER PART NUMBER") "RC0402FR-072K49L")
        (field (name "MANUFACTURER") "Yageo")
      )
      (libsource (lib "LimeMicroAltiumLib_schLib") (part "Res_0402"))
    )
    (comp (ref "RA5")
      (value "49.9R, 1%")
      (footprint "RES0402")
      (fields
        (field (name "TOLERANCE") "±1%")
        (field (name "MANUFACTURER") "Samsung Electro-Mechanics America, Inc.")
        (field (name "MANUFACTURER PART NUMBER") "RC1005F49R9CS")
      )
      (libsource (lib "LimeMicroAltiumLib_schLib") (part "Res_0402"))
    )
    (comp (ref "RA6")
      (value "49.9R, 1%")
      (footprint "RES0402")
      (fields
        (field (name "TOLERANCE") "±1%")
        (field (name "MANUFACTURER") "Samsung Electro-Mechanics America, Inc.")
        (field (name "MANUFACTURER PART NUMBER") "RC1005F49R9CS")
      )
      (libsource (lib "LimeMicroAltiumLib_schLib") (part "Res_0402"))
    )
    (comp (ref "RA7")
      (value "49.9R, 1%")
      (footprint "RES0402")
      (fields
        (field (name "TOLERANCE") "±1%")
        (field (name "MANUFACTURER") "Samsung Electro-Mechanics America, Inc.")
        (field (name "MANUFACTURER PART NUMBER") "RC1005F49R9CS")
      )
      (libsource (lib "LimeMicroAltiumLib_schLib") (part "Res_0402"))
    )
    (comp (ref "RA8")
      (value "49.9R, 1%")
      (footprint "RES0402")
      (fields
        (field (name "TOLERANCE") "±1%")
        (field (name "MANUFACTURER") "Samsung Electro-Mechanics America, Inc.")
        (field (name "MANUFACTURER PART NUMBER") "RC1005F49R9CS")
      )
      (libsource (lib "LimeMicroAltiumLib_schLib") (part "Res_0402"))
    )
    (comp (ref "RA9")
      (value "560R, 1%")
      (footprint "RES0402")
      (fields
        (field (name "MANUFACTURER PART NUMBER") "CRCW0402560RFKED")
        (field (name "TOLERANCE") "±1%")
        (field (name "MANUFACTURER") "Vishay Dale")
      )
      (libsource (lib "LimeMicroAltiumLib_schLib") (part "Res_0402"))
    )
    (comp (ref "RA10")
      (value "560R, 1%")
      (footprint "RES0402")
      (fields
        (field (name "MANUFACTURER PART NUMBER") "CRCW0402560RFKED")
        (field (name "TOLERANCE") "±1%")
        (field (name "MANUFACTURER") "Vishay Dale")
      )
      (libsource (lib "LimeMicroAltiumLib_schLib") (part "Res_0402"))
    )
    (comp (ref "RA11")
      (value "2.49k, 1%")
      (footprint "RES0402")
      (fields
        (field (name "TOLERANCE") "±1%")
        (field (name "MANUFACTURER PART NUMBER") "RC0402FR-072K49L")
        (field (name "MANUFACTURER") "Yageo")
      )
      (libsource (lib "LimeMicroAltiumLib_schLib") (part "Res_0402"))
    )
    (comp (ref "RA12")
      (value "2.49k, 1%")
      (footprint "RES0402")
      (fields
        (field (name "TOLERANCE") "±1%")
        (field (name "MANUFACTURER PART NUMBER") "RC0402FR-072K49L")
        (field (name "MANUFACTURER") "Yageo")
      )
      (libsource (lib "LimeMicroAltiumLib_schLib") (part "Res_0402"))
    )
    (comp (ref "RA13")
      (value "49.9R, 1%")
      (footprint "RES0402")
      (fields
        (field (name "TOLERANCE") "±1%")
        (field (name "MANUFACTURER") "Samsung Electro-Mechanics America, Inc.")
        (field (name "MANUFACTURER PART NUMBER") "RC1005F49R9CS")
      )
      (libsource (lib "LimeMicroAltiumLib_schLib") (part "Res_0402"))
    )
    (comp (ref "RA14")
      (value "49.9R, 1%")
      (footprint "RES0402")
      (fields
        (field (name "TOLERANCE") "±1%")
        (field (name "MANUFACTURER") "Samsung Electro-Mechanics America, Inc.")
        (field (name "MANUFACTURER PART NUMBER") "RC1005F49R9CS")
      )
      (libsource (lib "LimeMicroAltiumLib_schLib") (part "Res_0402"))
    )
    (comp (ref "RA15")
      (value "49.9R, 1%")
      (footprint "RES0402")
      (fields
        (field (name "TOLERANCE") "±1%")
        (field (name "MANUFACTURER") "Samsung Electro-Mechanics America, Inc.")
        (field (name "MANUFACTURER PART NUMBER") "RC1005F49R9CS")
      )
      (libsource (lib "LimeMicroAltiumLib_schLib") (part "Res_0402"))
    )
    (comp (ref "RA16")
      (value "49.9R, 1%")
      (footprint "RES0402")
      (fields
        (field (name "TOLERANCE") "±1%")
        (field (name "MANUFACTURER") "Samsung Electro-Mechanics America, Inc.")
        (field (name "MANUFACTURER PART NUMBER") "RC1005F49R9CS")
      )
      (libsource (lib "LimeMicroAltiumLib_schLib") (part "Res_0402"))
    )
    (comp (ref "VT1")
      (value "RF MOSFET")
      (footprint "BF1105R_SOT143R4")
      (fields (field (name "MANUFACTURER") "NXP Semiconductors"))
      (libsource (lib "LimeMicroAltiumLib_schLib") (part "BF1105R,215"))
    )
    (comp (ref "VT2")
      (value "RF MOSFET")
      (footprint "BF1105R_SOT143R4")
      (fields (field (name "MANUFACTURER") "NXP Semiconductors"))
      (libsource (lib "LimeMicroAltiumLib_schLib") (part "BF1105R,215"))
    )
    (comp (ref "VT3")
      (value "RF MOSFET")
      (footprint "BF1105R_SOT143R4")
      (fields (field (name "MANUFACTURER") "NXP Semiconductors"))
      (libsource (lib "LimeMicroAltiumLib_schLib") (part "BF1105R,215"))
    )
    (comp (ref "VT4")
      (value "RF MOSFET")
      (footprint "BF1105R_SOT143R4")
      (fields (field (name "MANUFACTURER") "NXP Semiconductors"))
      (libsource (lib "LimeMicroAltiumLib_schLib") (part "BF1105R,215"))
    )
    (comp (ref "VT5")
      (value "RF MOSFET")
      (footprint "BF1105R_SOT143R4")
      (fields (field (name "MANUFACTURER") "NXP Semiconductors"))
      (libsource (lib "LimeMicroAltiumLib_schLib") (part "BF1105R,215"))
    )
    (comp (ref "VT6")
      (value "RF MOSFET")
      (footprint "BF1105R_SOT143R4")
      (fields (field (name "MANUFACTURER") "NXP Semiconductors"))
      (libsource (lib "LimeMicroAltiumLib_schLib") (part "BF1105R,215"))
    )
    (comp (ref "VT7")
      (value "RF MOSFET")
      (footprint "BF1105R_SOT143R4")
      (fields (field (name "MANUFACTURER") "NXP Semiconductors"))
      (libsource (lib "LimeMicroAltiumLib_schLib") (part "BF1105R,215"))
    )
    (comp (ref "VT8")
      (value "RF MOSFET")
      (footprint "BF1105R_SOT143R4")
      (fields (field (name "MANUFACTURER") "NXP Semiconductors"))
      (libsource (lib "LimeMicroAltiumLib_schLib") (part "BF1105R,215"))
    )
    (comp (ref "VT9")
      (value "RF MOSFET")
      (footprint "BF1105R_SOT143R4")
      (fields (field (name "MANUFACTURER") "NXP Semiconductors"))
      (libsource (lib "LimeMicroAltiumLib_schLib") (part "BF1105R,215"))
    )
    (comp (ref "VT10")
      (value "RF MOSFET")
      (footprint "BF1105R_SOT143R4")
      (fields (field (name "MANUFACTURER") "NXP Semiconductors"))
      (libsource (lib "LimeMicroAltiumLib_schLib") (part "BF1105R,215"))
    )
    (comp (ref "VT11")
      (value "RF MOSFET")
      (footprint "BF1105R_SOT143R4")
      (fields (field (name "MANUFACTURER") "NXP Semiconductors"))
      (libsource (lib "LimeMicroAltiumLib_schLib") (part "BF1105R,215"))
    )
    (comp (ref "VT12")
      (value "RF MOSFET")
      (footprint "BF1105R_SOT143R4")
      (fields (field (name "MANUFACTURER") "NXP Semiconductors"))
      (libsource (lib "LimeMicroAltiumLib_schLib") (part "BF1105R,215"))
    )
  )
  (nets
    (net (code "1") (name "/FPGA_SPI2_SCLK") (class "Default")
      (node (ref "IC9") (pin "9") (pinfunction "B4_9") (pintype "passive"))
    )
    (net (code "2") (name "/FPGA_SPI2_SCLK_LS") (class "Default")
      (node (ref "IC9") (pin "4") (pinfunction "A4_4") (pintype "passive"))
    )
    (net (code "3") (name "/LMS1_LOOPBACK_RX1H") (class "Default")
      (node (ref "IC12") (pin "5") (pinfunction "RF_IN_5") (pintype "input"))
    )
    (net (code "4") (name "/LMS1_LOOPBACK_RX2H") (class "Default")
      (node (ref "IC16") (pin "5") (pinfunction "RF_IN_5") (pintype "input"))
    )
    (net (code "5") (name "/LMS1_LOOPBACK_TX12") (class "Default")
      (node (ref "IC10") (pin "5") (pinfunction "RF_IN_5") (pintype "input"))
    )
    (net (code "6") (name "/LMS1_LOOPBACK_TX22") (class "Default")
      (node (ref "IC14") (pin "5") (pinfunction "RF_IN_5") (pintype "input"))
    )
    (net (code "7") (name "/LMS1_TX1_2_LB_AT") (class "Default")
      (node (ref "C189") (pin "1") (pinfunction "1_1") (pintype "passive"))
      (node (ref "IC7") (pin "3") (pinfunction "Q3_3") (pintype "output"))
      (node (ref "R73") (pin "2") (pinfunction "2_2") (pintype "passive"))
    )
    (net (code "8") (name "/LMS1_TX1_2_LB_H") (class "Default")
      (node (ref "C183") (pin "2") (pinfunction "2_2") (pintype "passive"))
      (node (ref "C200") (pin "2") (pinfunction "2_2") (pintype "passive"))
      (node (ref "IC10") (pin "4") (pinfunction "VCTL2_4") (pintype "input"))
      (node (ref "IC12") (pin "6") (pinfunction "VCTL1_6") (pintype "input"))
      (node (ref "IC7") (pin "4") (pinfunction "Q4_4") (pintype "output"))
    )
    (net (code "9") (name "/LMS1_TX1_2_LB_L") (class "Default")
      (node (ref "C184") (pin "2") (pinfunction "2_2") (pintype "passive"))
      (node (ref "C199") (pin "2") (pinfunction "2_2") (pintype "passive"))
      (node (ref "IC10") (pin "6") (pinfunction "VCTL1_6") (pintype "input"))
      (node (ref "IC12") (pin "4") (pinfunction "VCTL2_4") (pintype "input"))
      (node (ref "IC7") (pin "5") (pinfunction "Q5_5") (pintype "output"))
    )
    (net (code "10") (name "/LMS1_TX1_2_LB_SH") (class "Default")
      (node (ref "C192") (pin "1") (pinfunction "1_1") (pintype "passive"))
      (node (ref "C194") (pin "1") (pinfunction "1_1") (pintype "passive"))
      (node (ref "IC7") (pin "2") (pinfunction "Q2_2") (pintype "output"))
      (node (ref "R77") (pin "2") (pinfunction "2_2") (pintype "passive"))
      (node (ref "R78") (pin "1") (pinfunction "1_1") (pintype "passive"))
    )
    (net (code "11") (name "/LMS1_TX2_2_LB_AT") (class "Default")
      (node (ref "C211") (pin "1") (pinfunction "1_1") (pintype "passive"))
      (node (ref "IC7") (pin "15") (pinfunction "Q0_15") (pintype "output"))
      (node (ref "R81") (pin "2") (pinfunction "2_2") (pintype "passive"))
    )
    (net (code "12") (name "/LMS1_TX2_2_LB_H") (class "Default")
      (node (ref "C205") (pin "2") (pinfunction "2_2") (pintype "passive"))
      (node (ref "C222") (pin "2") (pinfunction "2_2") (pintype "passive"))
      (node (ref "IC14") (pin "4") (pinfunction "VCTL2_4") (pintype "input"))
      (node (ref "IC16") (pin "6") (pinfunction "VCTL1_6") (pintype "input"))
      (node (ref "IC7") (pin "6") (pinfunction "Q6_6") (pintype "output"))
    )
    (net (code "13") (name "/LMS1_TX2_2_LB_L") (class "Default")
      (node (ref "C206") (pin "2") (pinfunction "2_2") (pintype "passive"))
      (node (ref "C221") (pin "2") (pinfunction "2_2") (pintype "passive"))
      (node (ref "IC14") (pin "6") (pinfunction "VCTL1_6") (pintype "input"))
      (node (ref "IC16") (pin "4") (pinfunction "VCTL2_4") (pintype "input"))
      (node (ref "IC7") (pin "7") (pinfunction "Q7_7") (pintype "output"))
    )
    (net (code "14") (name "/LMS1_TX2_2_LB_SH") (class "Default")
      (node (ref "C215") (pin "1") (pinfunction "1_1") (pintype "passive"))
      (node (ref "C216") (pin "1") (pinfunction "1_1") (pintype "passive"))
      (node (ref "IC7") (pin "1") (pinfunction "Q1_1") (pintype "output"))
      (node (ref "R85") (pin "1") (pinfunction "1_1") (pintype "passive"))
      (node (ref "R86") (pin "2") (pinfunction "2_2") (pintype "passive"))
    )
    (net (code "15") (name "/LMS2_LOOPBACK_RX1H") (class "Default")
      (node (ref "IC13") (pin "5") (pinfunction "RF_IN_5") (pintype "input"))
    )
    (net (code "16") (name "/LMS2_LOOPBACK_RX2H") (class "Default")
      (node (ref "IC17") (pin "5") (pinfunction "RF_IN_5") (pintype "input"))
    )
    (net (code "17") (name "/LMS2_LOOPBACK_TX12") (class "Default")
      (node (ref "IC11") (pin "5") (pinfunction "RF_IN_5") (pintype "input"))
    )
    (net (code "18") (name "/LMS2_LOOPBACK_TX22") (class "Default")
      (node (ref "IC15") (pin "5") (pinfunction "RF_IN_5") (pintype "input"))
    )
    (net (code "19") (name "/LMS2_TX1_2_LB_AT") (class "Default")
      (node (ref "C190") (pin "1") (pinfunction "1_1") (pintype "passive"))
      (node (ref "IC8") (pin "6") (pinfunction "Q6_6") (pintype "output"))
      (node (ref "R74") (pin "2") (pinfunction "2_2") (pintype "passive"))
    )
    (net (code "20") (name "/LMS2_TX1_2_LB_H") (class "Default")
      (node (ref "C186") (pin "2") (pinfunction "2_2") (pintype "passive"))
      (node (ref "C202") (pin "2") (pinfunction "2_2") (pintype "passive"))
      (node (ref "IC11") (pin "4") (pinfunction "VCTL2_4") (pintype "input"))
      (node (ref "IC13") (pin "6") (pinfunction "VCTL1_6") (pintype "input"))
      (node (ref "IC8") (pin "3") (pinfunction "Q3_3") (pintype "output"))
    )
    (net (code "21") (name "/LMS2_TX1_2_LB_L") (class "Default")
      (node (ref "C187") (pin "2") (pinfunction "2_2") (pintype "passive"))
      (node (ref "C201") (pin "2") (pinfunction "2_2") (pintype "passive"))
      (node (ref "IC11") (pin "6") (pinfunction "VCTL1_6") (pintype "input"))
      (node (ref "IC13") (pin "4") (pinfunction "VCTL2_4") (pintype "input"))
      (node (ref "IC8") (pin "2") (pinfunction "Q2_2") (pintype "output"))
    )
    (net (code "22") (name "/LMS2_TX1_2_LB_SH") (class "Default")
      (node (ref "C195") (pin "1") (pinfunction "1_1") (pintype "passive"))
      (node (ref "C196") (pin "1") (pinfunction "1_1") (pintype "passive"))
      (node (ref "IC8") (pin "5") (pinfunction "Q5_5") (pintype "output"))
      (node (ref "R79") (pin "2") (pinfunction "2_2") (pintype "passive"))
      (node (ref "R80") (pin "1") (pinfunction "1_1") (pintype "passive"))
    )
    (net (code "23") (name "/LMS2_TX2_2_LB_AT") (class "Default")
      (node (ref "C212") (pin "1") (pinfunction "1_1") (pintype "passive"))
      (node (ref "IC8") (pin "4") (pinfunction "Q4_4") (pintype "output"))
      (node (ref "R82") (pin "2") (pinfunction "2_2") (pintype "passive"))
    )
    (net (code "24") (name "/LMS2_TX2_2_LB_H") (class "Default")
      (node (ref "C208") (pin "2") (pinfunction "2_2") (pintype "passive"))
      (node (ref "C224") (pin "2") (pinfunction "2_2") (pintype "passive"))
      (node (ref "IC15") (pin "4") (pinfunction "VCTL2_4") (pintype "input"))
      (node (ref "IC17") (pin "6") (pinfunction "VCTL1_6") (pintype "input"))
      (node (ref "IC8") (pin "1") (pinfunction "Q1_1") (pintype "output"))
    )
    (net (code "25") (name "/LMS2_TX2_2_LB_L") (class "Default")
      (node (ref "C209") (pin "2") (pinfunction "2_2") (pintype "passive"))
      (node (ref "C223") (pin "2") (pinfunction "2_2") (pintype "passive"))
      (node (ref "IC15") (pin "6") (pinfunction "VCTL1_6") (pintype "input"))
      (node (ref "IC17") (pin "4") (pinfunction "VCTL2_4") (pintype "input"))
      (node (ref "IC8") (pin "15") (pinfunction "Q0_15") (pintype "output"))
    )
    (net (code "26") (name "/LMS2_TX2_2_LB_SH") (class "Default")
      (node (ref "C217") (pin "1") (pinfunction "1_1") (pintype "passive"))
      (node (ref "C218") (pin "1") (pinfunction "1_1") (pintype "passive"))
      (node (ref "IC8") (pin "7") (pinfunction "Q7_7") (pintype "output"))
      (node (ref "R87") (pin "1") (pinfunction "1_1") (pintype "passive"))
      (node (ref "R88") (pin "2") (pinfunction "2_2") (pintype "passive"))
    )
    (net (code "27") (name "/SR_DIN") (class "Default")
      (node (ref "IC7") (pin "14") (pinfunction "DS_14") (pintype "input"))
      (node (ref "IC9") (pin "12") (pinfunction "B1_12") (pintype "passive"))
    )
    (net (code "28") (name "/SR_DIN_LS") (class "Default")
      (node (ref "IC9") (pin "1") (pinfunction "A1_1") (pintype "passive"))
    )
    (net (code "29") (name "/SR_DOUT") (class "Default")
      (node (ref "IC7") (pin "9") (pinfunction "Q7S_9") (pintype "output"))
      (node (ref "IC8") (pin "14") (pinfunction "DS_14") (pintype "input"))
    )
    (net (code "30") (name "/SR_LATCH") (class "Default")
      (node (ref "IC7") (pin "12") (pinfunction "STCP_12") (pintype "input"))
      (node (ref "IC8") (pin "12") (pinfunction "STCP_12") (pintype "input"))
      (node (ref "IC9") (pin "10") (pinfunction "B3_10") (pintype "passive"))
    )
    (net (code "31") (name "/SR_LATCH_LS") (class "Default")
      (node (ref "IC9") (pin "3") (pinfunction "A3_3") (pintype "passive"))
    )
    (net (code "32") (name "/SR_SCLK") (class "Default")
      (node (ref "IC7") (pin "11") (pinfunction "SHCP_11") (pintype "input"))
      (node (ref "IC8") (pin "11") (pinfunction "SHCP_11") (pintype "input"))
      (node (ref "IC9") (pin "11") (pinfunction "B2_11") (pintype "passive"))
    )
    (net (code "33") (name "/SR_SCLK_LS") (class "Default")
      (node (ref "IC9") (pin "2") (pinfunction "A2_2") (pintype "passive"))
    )
    (net (code "34") (name "GND") (class "Default")
      (node (ref "C177") (pin "1") (pinfunction "1_1") (pintype "passive"))
      (node (ref "C178") (pin "1") (pinfunction "1_1") (pintype "passive"))
      (node (ref "C179") (pin "1") (pinfunction "1_1") (pintype "passive"))
      (node (ref "C180") (pin "1") (pinfunction "1_1") (pintype "passive"))
      (node (ref "C183") (pin "1") (pinfunction "1_1") (pintype "passive"))
      (node (ref "C184") (pin "1") (pinfunction "1_1") (pintype "passive"))
      (node (ref "C186") (pin "1") (pinfunction "1_1") (pintype "passive"))
      (node (ref "C187") (pin "1") (pinfunction "1_1") (pintype "passive"))
      (node (ref "C189") (pin "2") (pinfunction "2_2") (pintype "passive"))
      (node (ref "C190") (pin "2") (pinfunction "2_2") (pintype "passive"))
      (node (ref "C192") (pin "2") (pinfunction "2_2") (pintype "passive"))
      (node (ref "C194") (pin "2") (pinfunction "2_2") (pintype "passive"))
      (node (ref "C195") (pin "2") (pinfunction "2_2") (pintype "passive"))
      (node (ref "C196") (pin "2") (pinfunction "2_2") (pintype "passive"))
      (node (ref "C199") (pin "1") (pinfunction "1_1") (pintype "passive"))
      (node (ref "C200") (pin "1") (pinfunction "1_1") (pintype "passive"))
      (node (ref "C201") (pin "1") (pinfunction "1_1") (pintype "passive"))
      (node (ref "C202") (pin "1") (pinfunction "1_1") (pintype "passive"))
      (node (ref "C205") (pin "1") (pinfunction "1_1") (pintype "passive"))
      (node (ref "C206") (pin "1") (pinfunction "1_1") (pintype "passive"))
      (node (ref "C208") (pin "1") (pinfunction "1_1") (pintype "passive"))
      (node (ref "C209") (pin "1") (pinfunction "1_1") (pintype "passive"))
      (node (ref "C211") (pin "2") (pinfunction "2_2") (pintype "passive"))
      (node (ref "C212") (pin "2") (pinfunction "2_2") (pintype "passive"))
      (node (ref "C215") (pin "2") (pinfunction "2_2") (pintype "passive"))
      (node (ref "C216") (pin "2") (pinfunction "2_2") (pintype "passive"))
      (node (ref "C217") (pin "2") (pinfunction "2_2") (pintype "passive"))
      (node (ref "C218") (pin "2") (pinfunction "2_2") (pintype "passive"))
      (node (ref "C221") (pin "1") (pinfunction "1_1") (pintype "passive"))
      (node (ref "C222") (pin "1") (pinfunction "1_1") (pintype "passive"))
      (node (ref "C223") (pin "1") (pinfunction "1_1") (pintype "passive"))
      (node (ref "C224") (pin "1") (pinfunction "1_1") (pintype "passive"))
      (node (ref "ESD13") (pin "2") (pinfunction "2_2") (pintype "passive"))
      (node (ref "ESD14") (pin "2") (pinfunction "2_2") (pintype "passive"))
      (node (ref "ESD15") (pin "2") (pinfunction "2_2") (pintype "passive"))
      (node (ref "ESD16") (pin "2") (pinfunction "2_2") (pintype "passive"))
      (node (ref "ESD17") (pin "2") (pinfunction "2_2") (pintype "passive"))
      (node (ref "ESD18") (pin "2") (pinfunction "2_2") (pintype "passive"))
      (node (ref "ESD19") (pin "2") (pinfunction "2_2") (pintype "passive"))
      (node (ref "ESD20") (pin "2") (pinfunction "2_2") (pintype "passive"))
      (node (ref "IC10") (pin "2") (pinfunction "GND_2") (pintype "passive"))
      (node (ref "IC11") (pin "2") (pinfunction "GND_2") (pintype "passive"))
      (node (ref "IC12") (pin "2") (pinfunction "GND_2") (pintype "passive"))
      (node (ref "IC13") (pin "2") (pinfunction "GND_2") (pintype "passive"))
      (node (ref "IC14") (pin "2") (pinfunction "GND_2") (pintype "passive"))
      (node (ref "IC15") (pin "2") (pinfunction "GND_2") (pintype "passive"))
      (node (ref "IC16") (pin "2") (pinfunction "GND_2") (pintype "passive"))
      (node (ref "IC17") (pin "2") (pinfunction "GND_2") (pintype "passive"))
      (node (ref "IC7") (pin "13") (pinfunction "~{OE}_13") (pintype "input"))
      (node (ref "IC7") (pin "8") (pinfunction "GND_8") (pintype "passive"))
      (node (ref "IC7") (pin "PAD") (pinfunction "PAD_PAD") (pintype "passive"))
      (node (ref "IC8") (pin "13") (pinfunction "~{OE}_13") (pintype "input"))
      (node (ref "IC8") (pin "8") (pinfunction "GND_8") (pintype "passive"))
      (node (ref "IC8") (pin "PAD") (pinfunction "PAD_PAD") (pintype "passive"))
      (node (ref "IC9") (pin "7") (pinfunction "OE_7") (pintype "passive"))
      (node (ref "IC9") (pin "8") (pinfunction "GND_8") (pintype "passive"))
      (node (ref "J13") (pin "2") (pinfunction "Y_2") (pintype "passive"))
      (node (ref "J14") (pin "2") (pinfunction "Y_2") (pintype "passive"))
      (node (ref "J15") (pin "2") (pinfunction "Y_2") (pintype "passive"))
      (node (ref "J16") (pin "2") (pinfunction "Y_2") (pintype "passive"))
      (node (ref "J17") (pin "2") (pinfunction "Y_2") (pintype "passive"))
      (node (ref "J18") (pin "2") (pinfunction "Y_2") (pintype "passive"))
      (node (ref "J19") (pin "2") (pinfunction "Y_2") (pintype "passive"))
      (node (ref "J20") (pin "2") (pinfunction "Y_2") (pintype "passive"))
      (node (ref "MECH1") (pin "1") (pinfunction "GND_1") (pintype "passive"))
      (node (ref "MECH10") (pin "1") (pinfunction "GND_1") (pintype "passive"))
      (node (ref "MECH11") (pin "1") (pinfunction "GND_1") (pintype "passive"))
      (node (ref "MECH12") (pin "1") (pinfunction "GND_1") (pintype "passive"))
      (node (ref "MECH13") (pin "1") (pinfunction "GND_1") (pintype "passive"))
      (node (ref "MECH14") (pin "1") (pinfunction "GND_1") (pintype "passive"))
      (node (ref "MECH15") (pin "1") (pinfunction "GND_1") (pintype "passive"))
      (node (ref "MECH16") (pin "1") (pinfunction "GND_1") (pintype "passive"))
      (node (ref "MECH17") (pin "1") (pinfunction "GND_1") (pintype "passive"))
      (node (ref "MECH18") (pin "1") (pinfunction "GND_1") (pintype "passive"))
      (node (ref "MECH2") (pin "1") (pinfunction "GND_1") (pintype "passive"))
      (node (ref "MECH3") (pin "1") (pinfunction "GND_1") (pintype "passive"))
      (node (ref "MECH4") (pin "1") (pinfunction "GND_1") (pintype "passive"))
      (node (ref "MECH5") (pin "1") (pinfunction "GND_1") (pintype "passive"))
      (node (ref "MECH6") (pin "1") (pinfunction "GND_1") (pintype "passive"))
      (node (ref "MECH7") (pin "1") (pinfunction "GND_1") (pintype "passive"))
      (node (ref "MECH8") (pin "1") (pinfunction "GND_1") (pintype "passive"))
      (node (ref "MECH9") (pin "1") (pinfunction "GND_1") (pintype "passive"))
      (node (ref "RA13") (pin "1") (pinfunction "1_1") (pintype "passive"))
      (node (ref "RA14") (pin "1") (pinfunction "1_1") (pintype "passive"))
      (node (ref "RA15") (pin "1") (pinfunction "1_1") (pintype "passive"))
      (node (ref "RA16") (pin "1") (pinfunction "1_1") (pintype "passive"))
      (node (ref "RA5") (pin "1") (pinfunction "1_1") (pintype "passive"))
      (node (ref "RA6") (pin "1") (pinfunction "1_1") (pintype "passive"))
      (node (ref "RA7") (pin "1") (pinfunction "1_1") (pintype "passive"))
      (node (ref "RA8") (pin "1") (pinfunction "1_1") (pintype "passive"))
      (node (ref "VT10") (pin "1") (pinfunction "S_1") (pintype "passive"))
      (node (ref "VT11") (pin "1") (pinfunction "S_1") (pintype "passive"))
      (node (ref "VT12") (pin "1") (pinfunction "S_1") (pintype "passive"))
      (node (ref "VT3") (pin "1") (pinfunction "S_1") (pintype "passive"))
      (node (ref "VT4") (pin "1") (pinfunction "S_1") (pintype "passive"))
      (node (ref "VT5") (pin "1") (pinfunction "S_1") (pintype "passive"))
      (node (ref "VT6") (pin "1") (pinfunction "S_1") (pintype "passive"))
      (node (ref "VT9") (pin "1") (pinfunction "S_1") (pintype "passive"))
    )
    (net (code "35") (name "Net-(IC10-RF_OUT1)") (class "Default")
      (node (ref "C181") (pin "2") (pinfunction "2_2") (pintype "passive"))
      (node (ref "IC10") (pin "1") (pinfunction "RF_OUT1_1") (pintype "output"))
    )
    (net (code "36") (name "Net-(IC10-RF_OUT2)") (class "Default")
      (node (ref "C185") (pin "1") (pinfunction "1_1") (pintype "passive"))
      (node (ref "IC10") (pin "3") (pinfunction "RF_OUT2_3") (pintype "output"))
    )
    (net (code "37") (name "Net-(IC11-RF_OUT1)") (class "Default")
      (node (ref "C182") (pin "2") (pinfunction "2_2") (pintype "passive"))
      (node (ref "IC11") (pin "1") (pinfunction "RF_OUT1_1") (pintype "output"))
    )
    (net (code "38") (name "Net-(IC11-RF_OUT2)") (class "Default")
      (node (ref "C188") (pin "1") (pinfunction "1_1") (pintype "passive"))
      (node (ref "IC11") (pin "3") (pinfunction "RF_OUT2_3") (pintype "output"))
    )
    (net (code "39") (name "Net-(IC12-RF_OUT1)") (class "Default")
      (node (ref "C191") (pin "2") (pinfunction "2_2") (pintype "passive"))
      (node (ref "IC12") (pin "1") (pinfunction "RF_OUT1_1") (pintype "output"))
    )
    (net (code "40") (name "Net-(IC12-RF_OUT2)") (class "Default")
      (node (ref "C197") (pin "2") (pinfunction "2_2") (pintype "passive"))
      (node (ref "IC12") (pin "3") (pinfunction "RF_OUT2_3") (pintype "output"))
    )
    (net (code "41") (name "Net-(IC13-RF_OUT1)") (class "Default")
      (node (ref "C193") (pin "2") (pinfunction "2_2") (pintype "passive"))
      (node (ref "IC13") (pin "1") (pinfunction "RF_OUT1_1") (pintype "output"))
    )
    (net (code "42") (name "Net-(IC13-RF_OUT2)") (class "Default")
      (node (ref "C198") (pin "2") (pinfunction "2_2") (pintype "passive"))
      (node (ref "IC13") (pin "3") (pinfunction "RF_OUT2_3") (pintype "output"))
    )
    (net (code "43") (name "Net-(IC14-RF_OUT1)") (class "Default")
      (node (ref "C203") (pin "2") (pinfunction "2_2") (pintype "passive"))
      (node (ref "IC14") (pin "1") (pinfunction "RF_OUT1_1") (pintype "output"))
    )
    (net (code "44") (name "Net-(IC14-RF_OUT2)") (class "Default")
      (node (ref "C207") (pin "1") (pinfunction "1_1") (pintype "passive"))
      (node (ref "IC14") (pin "3") (pinfunction "RF_OUT2_3") (pintype "output"))
    )
    (net (code "45") (name "Net-(IC15-RF_OUT1)") (class "Default")
      (node (ref "C204") (pin "2") (pinfunction "2_2") (pintype "passive"))
      (node (ref "IC15") (pin "1") (pinfunction "RF_OUT1_1") (pintype "output"))
    )
    (net (code "46") (name "Net-(IC15-RF_OUT2)") (class "Default")
      (node (ref "C210") (pin "1") (pinfunction "1_1") (pintype "passive"))
      (node (ref "IC15") (pin "3") (pinfunction "RF_OUT2_3") (pintype "output"))
    )
    (net (code "47") (name "Net-(IC16-RF_OUT1)") (class "Default")
      (node (ref "C214") (pin "2") (pinfunction "2_2") (pintype "passive"))
      (node (ref "IC16") (pin "1") (pinfunction "RF_OUT1_1") (pintype "output"))
    )
    (net (code "48") (name "Net-(IC16-RF_OUT2)") (class "Default")
      (node (ref "C219") (pin "2") (pinfunction "2_2") (pintype "passive"))
      (node (ref "IC16") (pin "3") (pinfunction "RF_OUT2_3") (pintype "output"))
    )
    (net (code "49") (name "Net-(IC17-RF_OUT1)") (class "Default")
      (node (ref "C213") (pin "2") (pinfunction "2_2") (pintype "passive"))
      (node (ref "IC17") (pin "1") (pinfunction "RF_OUT1_1") (pintype "output"))
    )
    (net (code "50") (name "Net-(IC17-RF_OUT2)") (class "Default")
      (node (ref "C220") (pin "2") (pinfunction "2_2") (pintype "passive"))
      (node (ref "IC17") (pin "3") (pinfunction "RF_OUT2_3") (pintype "output"))
    )
    (net (code "51") (name "Net-(J13-X)") (class "Default")
      (node (ref "C181") (pin "1") (pinfunction "1_1") (pintype "passive"))
      (node (ref "ESD13") (pin "1") (pinfunction "1_1") (pintype "passive"))
      (node (ref "J13") (pin "1") (pinfunction "X_1") (pintype "passive"))
    )
    (net (code "52") (name "Net-(J14-X)") (class "Default")
      (node (ref "C182") (pin "1") (pinfunction "1_1") (pintype "passive"))
      (node (ref "ESD14") (pin "1") (pinfunction "1_1") (pintype "passive"))
      (node (ref "J14") (pin "1") (pinfunction "X_1") (pintype "passive"))
    )
    (net (code "53") (name "Net-(J15-X)") (class "Default")
      (node (ref "C197") (pin "1") (pinfunction "1_1") (pintype "passive"))
      (node (ref "ESD15") (pin "1") (pinfunction "1_1") (pintype "passive"))
      (node (ref "J15") (pin "1") (pinfunction "X_1") (pintype "passive"))
    )
    (net (code "54") (name "Net-(J16-X)") (class "Default")
      (node (ref "C198") (pin "1") (pinfunction "1_1") (pintype "passive"))
      (node (ref "ESD16") (pin "1") (pinfunction "1_1") (pintype "passive"))
      (node (ref "J16") (pin "1") (pinfunction "X_1") (pintype "passive"))
    )
    (net (code "55") (name "Net-(J17-X)") (class "Default")
      (node (ref "C203") (pin "1") (pinfunction "1_1") (pintype "passive"))
      (node (ref "ESD17") (pin "1") (pinfunction "1_1") (pintype "passive"))
      (node (ref "J17") (pin "1") (pinfunction "X_1") (pintype "passive"))
    )
    (net (code "56") (name "Net-(J18-X)") (class "Default")
      (node (ref "C204") (pin "1") (pinfunction "1_1") (pintype "passive"))
      (node (ref "ESD18") (pin "1") (pinfunction "1_1") (pintype "passive"))
      (node (ref "J18") (pin "1") (pinfunction "X_1") (pintype "passive"))
    )
    (net (code "57") (name "Net-(J19-X)") (class "Default")
      (node (ref "C220") (pin "1") (pinfunction "1_1") (pintype "passive"))
      (node (ref "ESD19") (pin "1") (pinfunction "1_1") (pintype "passive"))
      (node (ref "J19") (pin "1") (pinfunction "X_1") (pintype "passive"))
    )
    (net (code "58") (name "Net-(J20-X)") (class "Default")
      (node (ref "C219") (pin "1") (pinfunction "1_1") (pintype "passive"))
      (node (ref "ESD20") (pin "1") (pinfunction "1_1") (pintype "passive"))
      (node (ref "J20") (pin "1") (pinfunction "X_1") (pintype "passive"))
    )
    (net (code "59") (name "Net-(VT1-D)") (class "Default")
      (node (ref "RA1") (pin "2") (pinfunction "2_2") (pintype "passive"))
      (node (ref "VT1") (pin "2") (pinfunction "D_2") (pintype "passive"))
    )
    (net (code "60") (name "Net-(VT1-G1)") (class "Default")
      (node (ref "R73") (pin "1") (pinfunction "1_1") (pintype "passive"))
      (node (ref "VT1") (pin "3") (pinfunction "G2_3") (pintype "passive"))
      (node (ref "VT1") (pin "4") (pinfunction "G1_4") (pintype "passive"))
    )
    (net (code "61") (name "Net-(VT1-S)") (class "Default")
      (node (ref "C185") (pin "2") (pinfunction "2_2") (pintype "passive"))
      (node (ref "R75") (pin "1") (pinfunction "1_1") (pintype "passive"))
      (node (ref "RA3") (pin "1") (pinfunction "1_1") (pintype "passive"))
      (node (ref "RA5") (pin "2") (pinfunction "2_2") (pintype "passive"))
      (node (ref "VT1") (pin "1") (pinfunction "S_1") (pintype "passive"))
      (node (ref "VT4") (pin "2") (pinfunction "D_2") (pintype "passive"))
    )
    (net (code "62") (name "Net-(VT2-D)") (class "Default")
      (node (ref "RA2") (pin "2") (pinfunction "2_2") (pintype "passive"))
      (node (ref "VT2") (pin "2") (pinfunction "D_2") (pintype "passive"))
    )
    (net (code "63") (name "Net-(VT2-G1)") (class "Default")
      (node (ref "R74") (pin "1") (pinfunction "1_1") (pintype "passive"))
      (node (ref "VT2") (pin "3") (pinfunction "G2_3") (pintype "passive"))
      (node (ref "VT2") (pin "4") (pinfunction "G1_4") (pintype "passive"))
    )
    (net (code "64") (name "Net-(VT2-S)") (class "Default")
      (node (ref "C188") (pin "2") (pinfunction "2_2") (pintype "passive"))
      (node (ref "R76") (pin "1") (pinfunction "1_1") (pintype "passive"))
      (node (ref "RA4") (pin "1") (pinfunction "1_1") (pintype "passive"))
      (node (ref "RA7") (pin "2") (pinfunction "2_2") (pintype "passive"))
      (node (ref "VT2") (pin "1") (pinfunction "S_1") (pintype "passive"))
      (node (ref "VT6") (pin "2") (pinfunction "D_2") (pintype "passive"))
    )
    (net (code "65") (name "Net-(VT3-D)") (class "Default")
      (node (ref "C191") (pin "1") (pinfunction "1_1") (pintype "passive"))
      (node (ref "RA1") (pin "1") (pinfunction "1_1") (pintype "passive"))
      (node (ref "RA3") (pin "2") (pinfunction "2_2") (pintype "passive"))
      (node (ref "RA6") (pin "2") (pinfunction "2_2") (pintype "passive"))
      (node (ref "VT3") (pin "2") (pinfunction "D_2") (pintype "passive"))
    )
    (net (code "66") (name "Net-(VT3-G1)") (class "Default")
      (node (ref "R78") (pin "2") (pinfunction "2_2") (pintype "passive"))
      (node (ref "VT3") (pin "3") (pinfunction "G2_3") (pintype "passive"))
      (node (ref "VT3") (pin "4") (pinfunction "G1_4") (pintype "passive"))
    )
    (net (code "67") (name "Net-(VT4-G1)") (class "Default")
      (node (ref "R77") (pin "1") (pinfunction "1_1") (pintype "passive"))
      (node (ref "VT4") (pin "3") (pinfunction "G2_3") (pintype "passive"))
      (node (ref "VT4") (pin "4") (pinfunction "G1_4") (pintype "passive"))
    )
    (net (code "68") (name "Net-(VT5-D)") (class "Default")
      (node (ref "C193") (pin "1") (pinfunction "1_1") (pintype "passive"))
      (node (ref "RA2") (pin "1") (pinfunction "1_1") (pintype "passive"))
      (node (ref "RA4") (pin "2") (pinfunction "2_2") (pintype "passive"))
      (node (ref "RA8") (pin "2") (pinfunction "2_2") (pintype "passive"))
      (node (ref "VT5") (pin "2") (pinfunction "D_2") (pintype "passive"))
    )
    (net (code "69") (name "Net-(VT5-G1)") (class "Default")
      (node (ref "R80") (pin "2") (pinfunction "2_2") (pintype "passive"))
      (node (ref "VT5") (pin "3") (pinfunction "G2_3") (pintype "passive"))
      (node (ref "VT5") (pin "4") (pinfunction "G1_4") (pintype "passive"))
    )
    (net (code "70") (name "Net-(VT6-G1)") (class "Default")
      (node (ref "R79") (pin "1") (pinfunction "1_1") (pintype "passive"))
      (node (ref "VT6") (pin "3") (pinfunction "G2_3") (pintype "passive"))
      (node (ref "VT6") (pin "4") (pinfunction "G1_4") (pintype "passive"))
    )
    (net (code "71") (name "Net-(VT7-D)") (class "Default")
      (node (ref "RA9") (pin "2") (pinfunction "2_2") (pintype "passive"))
      (node (ref "VT7") (pin "2") (pinfunction "D_2") (pintype "passive"))
    )
    (net (code "72") (name "Net-(VT7-G1)") (class "Default")
      (node (ref "R81") (pin "1") (pinfunction "1_1") (pintype "passive"))
      (node (ref "VT7") (pin "3") (pinfunction "G2_3") (pintype "passive"))
      (node (ref "VT7") (pin "4") (pinfunction "G1_4") (pintype "passive"))
    )
    (net (code "73") (name "Net-(VT8-D)") (class "Default")
      (node (ref "RA10") (pin "2") (pinfunction "2_2") (pintype "passive"))
      (node (ref "VT8") (pin "2") (pinfunction "D_2") (pintype "passive"))
    )
    (net (code "74") (name "Net-(VT8-G1)") (class "Default")
      (node (ref "R82") (pin "1") (pinfunction "1_1") (pintype "passive"))
      (node (ref "VT8") (pin "3") (pinfunction "G2_3") (pintype "passive"))
      (node (ref "VT8") (pin "4") (pinfunction "G1_4") (pintype "passive"))
    )
    (net (code "75") (name "Net-(VT9-D)") (class "Default")
      (node (ref "C214") (pin "1") (pinfunction "1_1") (pintype "passive"))
      (node (ref "RA11") (pin "2") (pinfunction "2_2") (pintype "passive"))
      (node (ref "RA14") (pin "2") (pinfunction "2_2") (pintype "passive"))
      (node (ref "RA9") (pin "1") (pinfunction "1_1") (pintype "passive"))
      (node (ref "VT9") (pin "2") (pinfunction "D_2") (pintype "passive"))
    )
    (net (code "76") (name "Net-(VT9-G1)") (class "Default")
      (node (ref "R85") (pin "2") (pinfunction "2_2") (pintype "passive"))
      (node (ref "VT9") (pin "3") (pinfunction "G2_3") (pintype "passive"))
      (node (ref "VT9") (pin "4") (pinfunction "G1_4") (pintype "passive"))
    )
    (net (code "77") (name "Net-(VT10-D)") (class "Default")
      (node (ref "C207") (pin "2") (pinfunction "2_2") (pintype "passive"))
      (node (ref "R83") (pin "1") (pinfunction "1_1") (pintype "passive"))
      (node (ref "RA11") (pin "1") (pinfunction "1_1") (pintype "passive"))
      (node (ref "RA13") (pin "2") (pinfunction "2_2") (pintype "passive"))
      (node (ref "VT10") (pin "2") (pinfunction "D_2") (pintype "passive"))
      (node (ref "VT7") (pin "1") (pinfunction "S_1") (pintype "passive"))
    )
    (net (code "78") (name "Net-(VT10-G1)") (class "Default")
      (node (ref "R86") (pin "1") (pinfunction "1_1") (pintype "passive"))
      (node (ref "VT10") (pin "3") (pinfunction "G2_3") (pintype "passive"))
      (node (ref "VT10") (pin "4") (pinfunction "G1_4") (pintype "passive"))
    )
    (net (code "79") (name "Net-(VT11-D)") (class "Default")
      (node (ref "C213") (pin "1") (pinfunction "1_1") (pintype "passive"))
      (node (ref "RA10") (pin "1") (pinfunction "1_1") (pintype "passive"))
      (node (ref "RA12") (pin "2") (pinfunction "2_2") (pintype "passive"))
      (node (ref "RA16") (pin "2") (pinfunction "2_2") (pintype "passive"))
      (node (ref "VT11") (pin "2") (pinfunction "D_2") (pintype "passive"))
    )
    (net (code "80") (name "Net-(VT11-G1)") (class "Default")
      (node (ref "R87") (pin "2") (pinfunction "2_2") (pintype "passive"))
      (node (ref "VT11") (pin "3") (pinfunction "G2_3") (pintype "passive"))
      (node (ref "VT11") (pin "4") (pinfunction "G1_4") (pintype "passive"))
    )
    (net (code "81") (name "Net-(VT12-D)") (class "Default")
      (node (ref "C210") (pin "2") (pinfunction "2_2") (pintype "passive"))
      (node (ref "R84") (pin "1") (pinfunction "1_1") (pintype "passive"))
      (node (ref "RA12") (pin "1") (pinfunction "1_1") (pintype "passive"))
      (node (ref "RA15") (pin "2") (pinfunction "2_2") (pintype "passive"))
      (node (ref "VT12") (pin "2") (pinfunction "D_2") (pintype "passive"))
      (node (ref "VT8") (pin "1") (pinfunction "S_1") (pintype "passive"))
    )
    (net (code "82") (name "Net-(VT12-G1)") (class "Default")
      (node (ref "R88") (pin "1") (pinfunction "1_1") (pintype "passive"))
      (node (ref "VT12") (pin "3") (pinfunction "G2_3") (pintype "passive"))
      (node (ref "VT12") (pin "4") (pinfunction "G1_4") (pintype "passive"))
    )
    (net (code "83") (name "VCC1P5") (class "Default")
      (node (ref "C177") (pin "2") (pinfunction "2_2") (pintype "passive"))
      (node (ref "IC9") (pin "14") (pinfunction "VCCA_14") (pintype "passive"))
      (node (ref "IC9") (pin "15") (pinfunction "DIR1_15") (pintype "passive"))
      (node (ref "IC9") (pin "16") (pinfunction "DIR2_16") (pintype "passive"))
      (node (ref "IC9") (pin "5") (pinfunction "DIR3_5") (pintype "passive"))
      (node (ref "IC9") (pin "6") (pinfunction "DIR4_6") (pintype "passive"))
    )
    (net (code "84") (name "VCC1P8_LMS") (class "Default")
      (node (ref "R75") (pin "2") (pinfunction "2_2") (pintype "passive"))
      (node (ref "R76") (pin "2") (pinfunction "2_2") (pintype "passive"))
      (node (ref "R83") (pin "2") (pinfunction "2_2") (pintype "passive"))
      (node (ref "R84") (pin "2") (pinfunction "2_2") (pintype "passive"))
    )
    (net (code "85") (name "VCC3P3") (class "Default")
      (node (ref "C178") (pin "2") (pinfunction "2_2") (pintype "passive"))
      (node (ref "C179") (pin "2") (pinfunction "2_2") (pintype "passive"))
      (node (ref "C180") (pin "2") (pinfunction "2_2") (pintype "passive"))
      (node (ref "IC7") (pin "10") (pinfunction "~{MR}_10") (pintype "input"))
      (node (ref "IC7") (pin "16") (pinfunction "VCC_16") (pintype "power_in"))
      (node (ref "IC8") (pin "10") (pinfunction "~{MR}_10") (pintype "input"))
      (node (ref "IC8") (pin "16") (pinfunction "VCC_16") (pintype "power_in"))
      (node (ref "IC9") (pin "13") (pinfunction "VCCB_13") (pintype "passive"))
    )
    (net (code "86") (name "unconnected-(IC8-Q7S-Pad9)") (class "Default")
      (node (ref "IC8") (pin "9") (pinfunction "Q7S_9") (pintype "output+no_connect"))
    )
  )
)
